# ball_speed_sensor.net
KiCad netlist of a schematic drawn in EAGLE
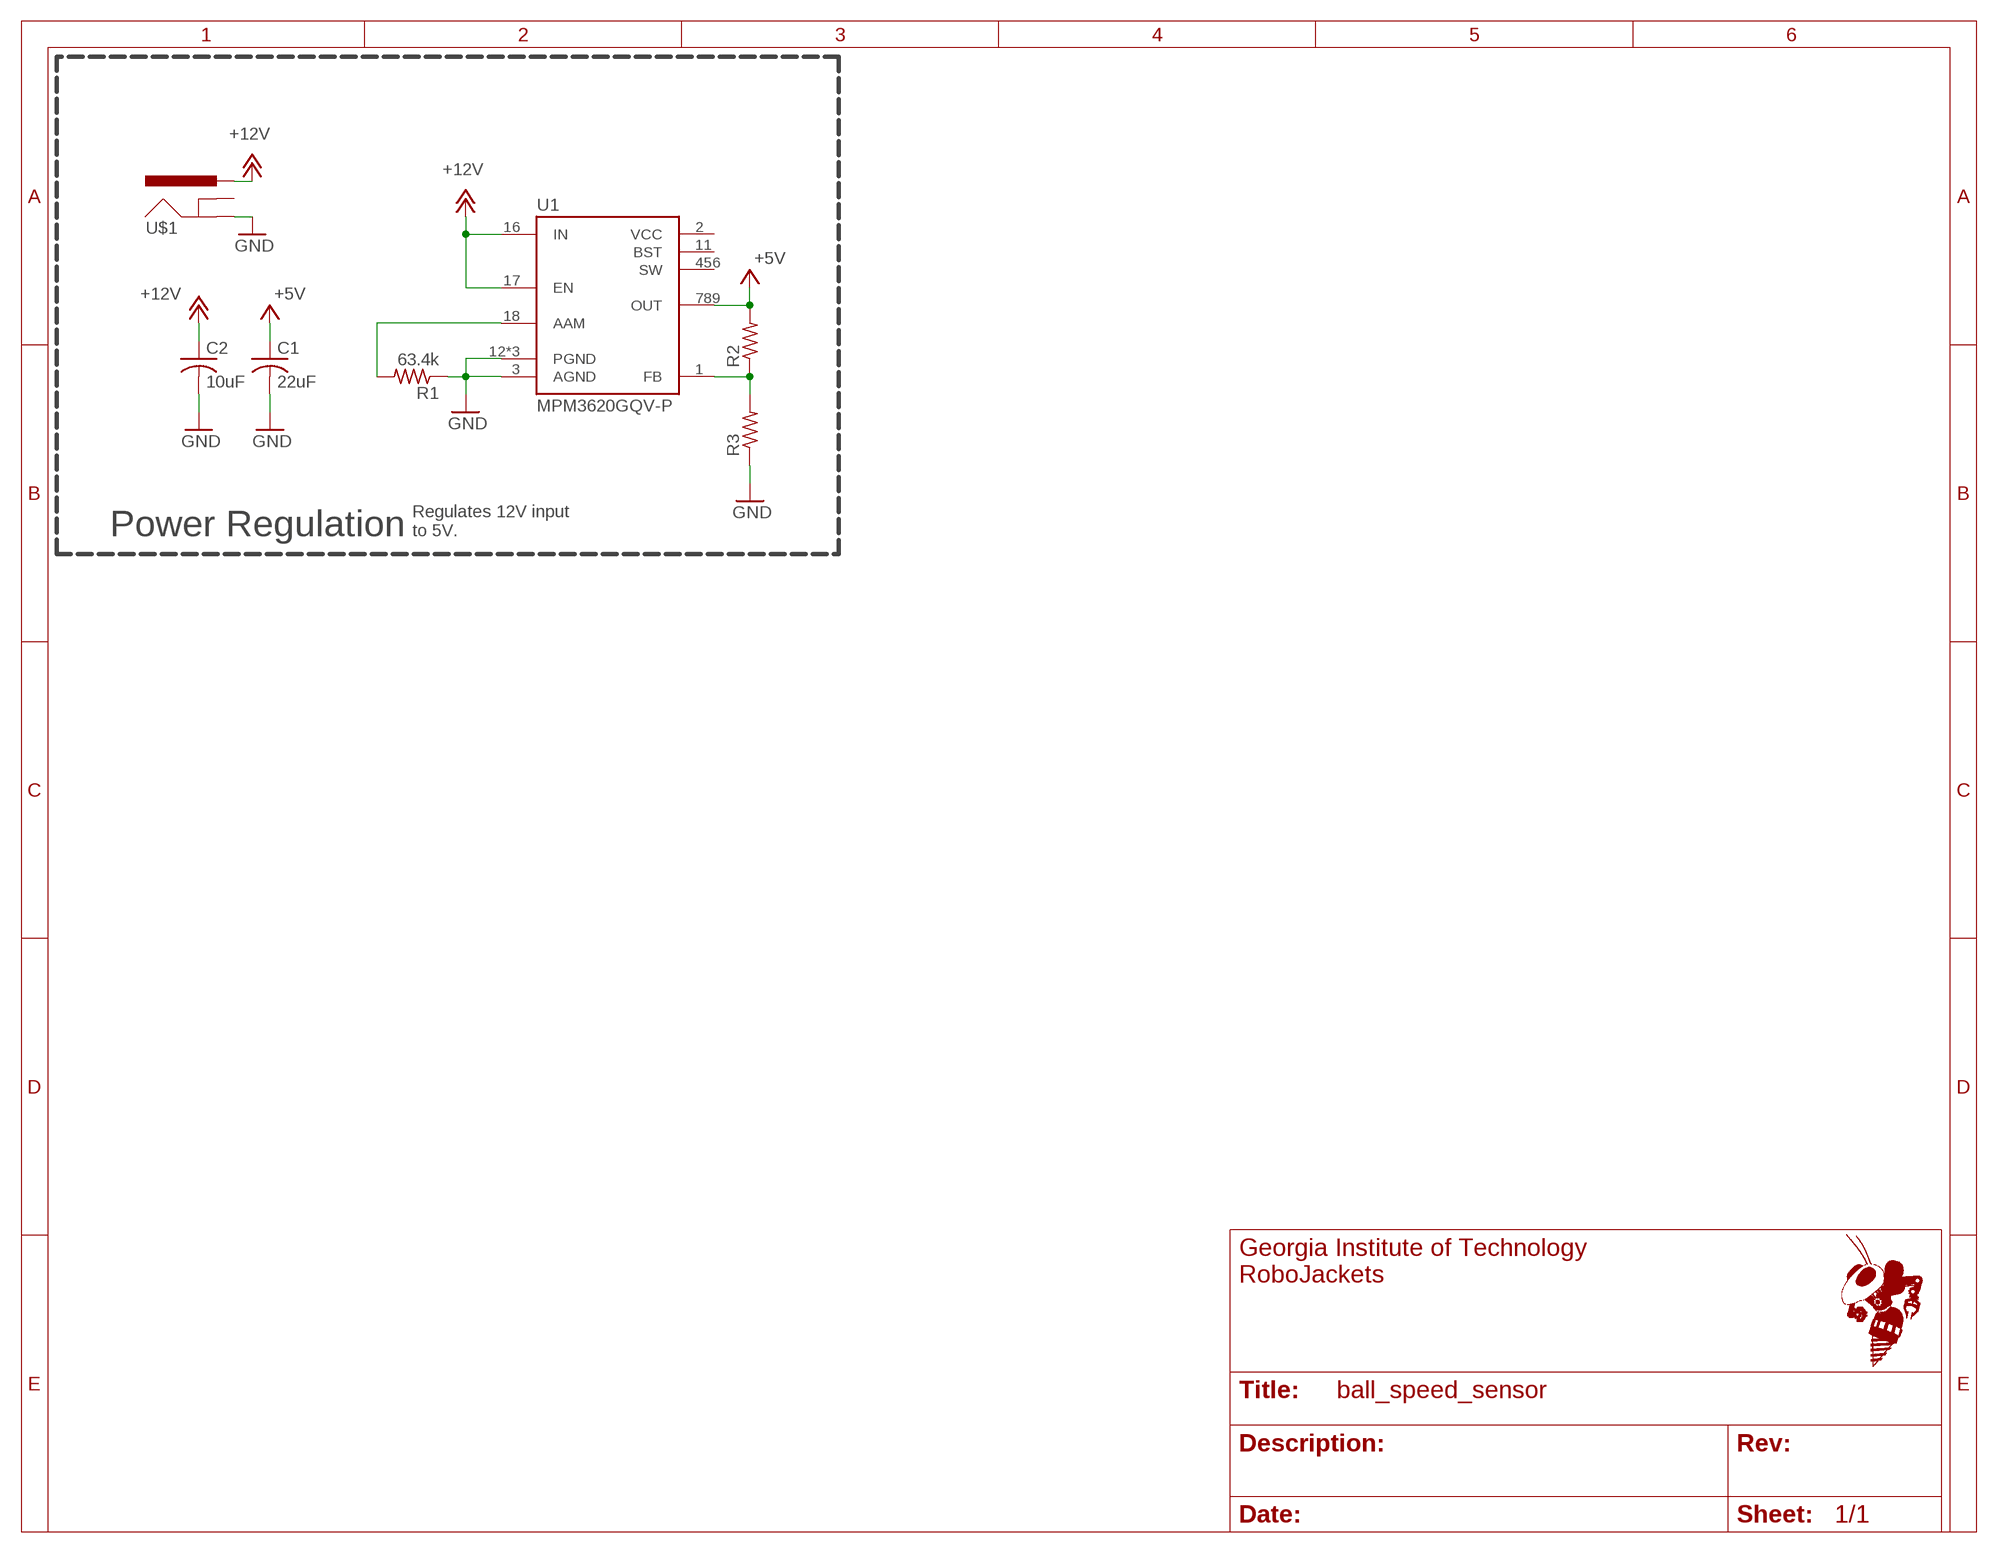
[diagram p0: schematic, sheet 1]

(export (version "E")
  (design (tool "Eeschema 10.0.6"))
  (components
    (comp (ref "C1")
      (value "22uF")
      (footprint "eagle-import:C0603")
      (libsource (lib "eagle-import") (part "C-USC0603"))
    )
    (comp (ref "C2")
      (value "10uF")
      (footprint "eagle-import:C0603")
      (libsource (lib "eagle-import") (part "C-USC0603"))
    )
    (comp (ref "R1")
      (value "63.4k")
      (footprint "eagle-import:R0603")
      (libsource (lib "eagle-import") (part "R-US_R0603"))
    )
    (comp (ref "R2")
      (value "R-US_R0603")
      (footprint "eagle-import:R0603")
      (libsource (lib "eagle-import") (part "R-US_R0603"))
    )
    (comp (ref "R3")
      (value "R-US_R0603")
      (footprint "eagle-import:R0603")
      (libsource (lib "eagle-import") (part "R-US_R0603"))
    )
    (comp (ref "U$1")
      (value "POWERJACK-2.1MM")
      (footprint "eagle-import:POWER_JACK_PTH")
      (libsource (lib "eagle-import") (part "POWERJACK-2.1MM"))
    )
    (comp (ref "U1")
      (value "MPM3620GQV-P")
      (footprint "eagle-import:MPM3620GQV-P")
      (libsource (lib "eagle-import") (part "MPM3620GQV-P"))
    )
  )
  (nets
    (net (code "1") (name "+5V") (class "Default")
      (node (ref "C1") (pin "1") (pinfunction "1_1") (pintype "passive"))
      (node (ref "R2") (pin "2") (pinfunction "2_2") (pintype "passive"))
      (node (ref "U1") (pin "789") (pinfunction "OUT_789") (pintype "bidirectional"))
    )
    (net (code "2") (name "+12V") (class "Default")
      (node (ref "C2") (pin "1") (pinfunction "1_1") (pintype "passive"))
      (node (ref "U$1") (pin "PWR") (pinfunction "PWR_PWR") (pintype "bidirectional"))
      (node (ref "U1") (pin "16") (pinfunction "IN_16") (pintype "bidirectional"))
      (node (ref "U1") (pin "17") (pinfunction "EN_17") (pintype "bidirectional"))
    )
    (net (code "3") (name "GND") (class "Default")
      (node (ref "C1") (pin "2") (pinfunction "2_2") (pintype "passive"))
      (node (ref "C2") (pin "2") (pinfunction "2_2") (pintype "passive"))
      (node (ref "R1") (pin "1") (pinfunction "1_1") (pintype "passive"))
      (node (ref "R3") (pin "1") (pinfunction "1_1") (pintype "passive"))
      (node (ref "U$1") (pin "GND") (pinfunction "GND_GND") (pintype "bidirectional"))
      (node (ref "U1") (pin "12") (pinfunction "PGND_12") (pintype "bidirectional"))
      (node (ref "U1") (pin "13") (pinfunction "PGND_13") (pintype "bidirectional"))
      (node (ref "U1") (pin "14") (pinfunction "PGND_14") (pintype "bidirectional"))
      (node (ref "U1") (pin "3") (pinfunction "AGND_3") (pintype "bidirectional"))
    )
    (net (code "4") (name "Net-(U1-AAM)") (class "Default")
      (node (ref "R1") (pin "2") (pinfunction "2_2") (pintype "passive"))
      (node (ref "U1") (pin "18") (pinfunction "AAM_18") (pintype "bidirectional"))
    )
    (net (code "5") (name "Net-(U1-FB)") (class "Default")
      (node (ref "R2") (pin "1") (pinfunction "1_1") (pintype "passive"))
      (node (ref "R3") (pin "2") (pinfunction "2_2") (pintype "passive"))
      (node (ref "U1") (pin "1") (pinfunction "FB_1") (pintype "bidirectional"))
    )
    (net (code "6") (name "unconnected-(U$1-PadGNDBREAK)") (class "Default")
      (node (ref "U$1") (pin "GNDBREAK") (pinfunction "GNDBREAK_GNDBREAK") (pintype "bidirectional"))
    )
    (net (code "7") (name "unconnected-(U1-BST-Pad11)") (class "Default")
      (node (ref "U1") (pin "11") (pinfunction "BST_11") (pintype "bidirectional"))
    )
    (net (code "8") (name "unconnected-(U1-SW-Pad456)") (class "Default")
      (node (ref "U1") (pin "456") (pinfunction "SW_456") (pintype "bidirectional"))
    )
    (net (code "9") (name "unconnected-(U1-VCC-Pad2)") (class "Default")
      (node (ref "U1") (pin "2") (pinfunction "VCC_2") (pintype "bidirectional"))
    )
  )
)
